# CANsetup.net
KiCad netlist of a schematic drawn in Altium Designer
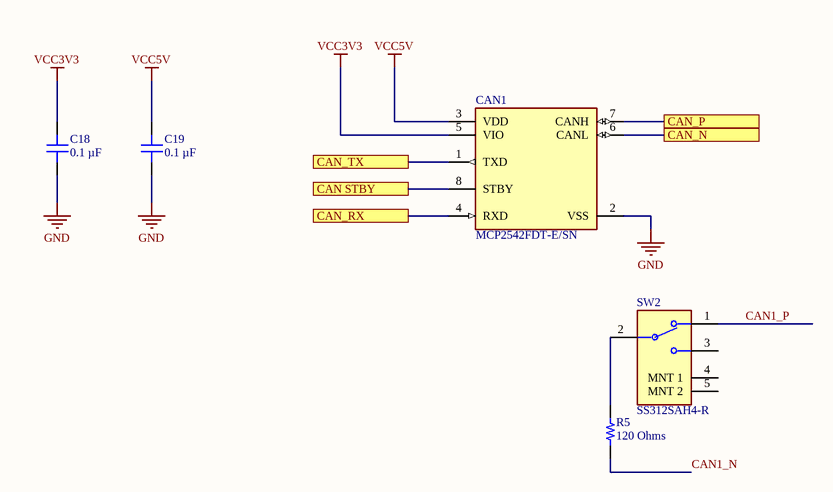
[diagram p0: CANsetup.SchDoc]

(export (version "E")
  (design (tool "Eeschema 10.0.6"))
  (components
    (comp (ref "C18")
      (value "0.1 µF")
      (footprint "CAP 01005_0402")
      (description "CAP CER 0.1UF 6.3V X5R 01005")
      (fields
        (field (name "PART NUMBER") "CL02A104KQ2NNNC")
        (field (name "MANUFACTURER") "Samsung Electro-Mechanics")
      )
      (libsource (lib "Celestial Altium Library - altium_library") (part "Capacitor"))
    )
    (comp (ref "C19")
      (value "0.1 µF")
      (footprint "CAP 01005_0402")
      (description "CAP CER 0.1UF 6.3V X5R 01005")
      (fields
        (field (name "PART NUMBER") "CL02A104KQ2NNNC")
        (field (name "MANUFACTURER") "Samsung Electro-Mechanics")
      )
      (libsource (lib "Celestial Altium Library - altium_library") (part "Capacitor"))
    )
    (comp (ref "CAN1")
      (value "MCP2542FDT-E/SN")
      (footprint "FP-C04-057-SN-IPC_C")
      (description "IC TRANSCEIVER 1/1 8SOIC")
      (libsource (lib "Altium Content Vault") (part "c0b3786e5a25f542f02164a957bd85f"))
    )
    (comp (ref "R5")
      (value "120 Ohms")
      (footprint "RES 0201_0603")
      (description "RES 120 OHM 5% 1/20W 0201")
      (fields
        (field (name "PART NUMBER") "RMCF0201JT120R")
        (field (name "MANUFACTURER") "Stackpole Electronics Inc")
      )
      (libsource (lib "Celestial Altium Library - altium_library") (part "Resistor"))
    )
    (comp (ref "SW2")
      (value "SS312SAH4-R")
      (footprint "FP-SS312SAH4-R-MFG")
      (description "SWITCH SLIDE SPDT 0.4VA 28V")
      (libsource (lib "Altium Content Vault") (part "4c976abc4051e389b5557946779e9a3"))
    )
  )
  (nets
    (net (code "1") (name "/CAN STBY") (class "Default")
      (node (ref "CAN1") (pin "8") (pinfunction "STBY_8") (pintype "passive"))
    )
    (net (code "2") (name "/CAN1_N") (class "Default")
      (node (ref "R5") (pin "2") (pinfunction "2_2") (pintype "passive"))
    )
    (net (code "3") (name "/CAN1_P") (class "Default")
      (node (ref "SW2") (pin "1") (pinfunction "1_1") (pintype "passive"))
    )
    (net (code "4") (name "/CAN_N") (class "Default")
      (node (ref "CAN1") (pin "6") (pinfunction "CANL_6") (pintype "bidirectional"))
    )
    (net (code "5") (name "/CAN_P") (class "Default")
      (node (ref "CAN1") (pin "7") (pinfunction "CANH_7") (pintype "bidirectional"))
    )
    (net (code "6") (name "/CAN_RX") (class "Default")
      (node (ref "CAN1") (pin "4") (pinfunction "RXD_4") (pintype "input"))
    )
    (net (code "7") (name "/CAN_TX") (class "Default")
      (node (ref "CAN1") (pin "1") (pinfunction "TXD_1") (pintype "output"))
    )
    (net (code "8") (name "GND") (class "Default")
      (node (ref "C18") (pin "2") (pinfunction "2_2") (pintype "passive"))
      (node (ref "C19") (pin "2") (pinfunction "2_2") (pintype "passive"))
      (node (ref "CAN1") (pin "2") (pinfunction "VSS_2") (pintype "power_in"))
    )
    (net (code "9") (name "Net-(SW2-COM)") (class "Default")
      (node (ref "R5") (pin "1") (pinfunction "1_1") (pintype "passive"))
      (node (ref "SW2") (pin "2") (pinfunction "COM_2") (pintype "passive"))
    )
    (net (code "10") (name "VCC3V3") (class "Default")
      (node (ref "C18") (pin "1") (pinfunction "1_1") (pintype "passive"))
      (node (ref "CAN1") (pin "5") (pinfunction "VIO_5") (pintype "power_in"))
    )
    (net (code "11") (name "VCC5V") (class "Default")
      (node (ref "C19") (pin "1") (pinfunction "1_1") (pintype "passive"))
      (node (ref "CAN1") (pin "3") (pinfunction "VDD_3") (pintype "power_in"))
    )
    (net (code "12") (name "unconnected-(SW2-MNT_1-Pad4)") (class "Default")
      (node (ref "SW2") (pin "4") (pinfunction "MNT_1_4") (pintype "passive"))
    )
    (net (code "13") (name "unconnected-(SW2-MNT_2-Pad5)") (class "Default")
      (node (ref "SW2") (pin "5") (pinfunction "MNT_2_5") (pintype "passive"))
    )
    (net (code "14") (name "unconnected-(SW2-Pad3)") (class "Default")
      (node (ref "SW2") (pin "3") (pinfunction "3_3") (pintype "passive"))
    )
  )
)
